# SX1276_e268v01a.net
KiCad netlist of a schematic drawn in Altium Designer
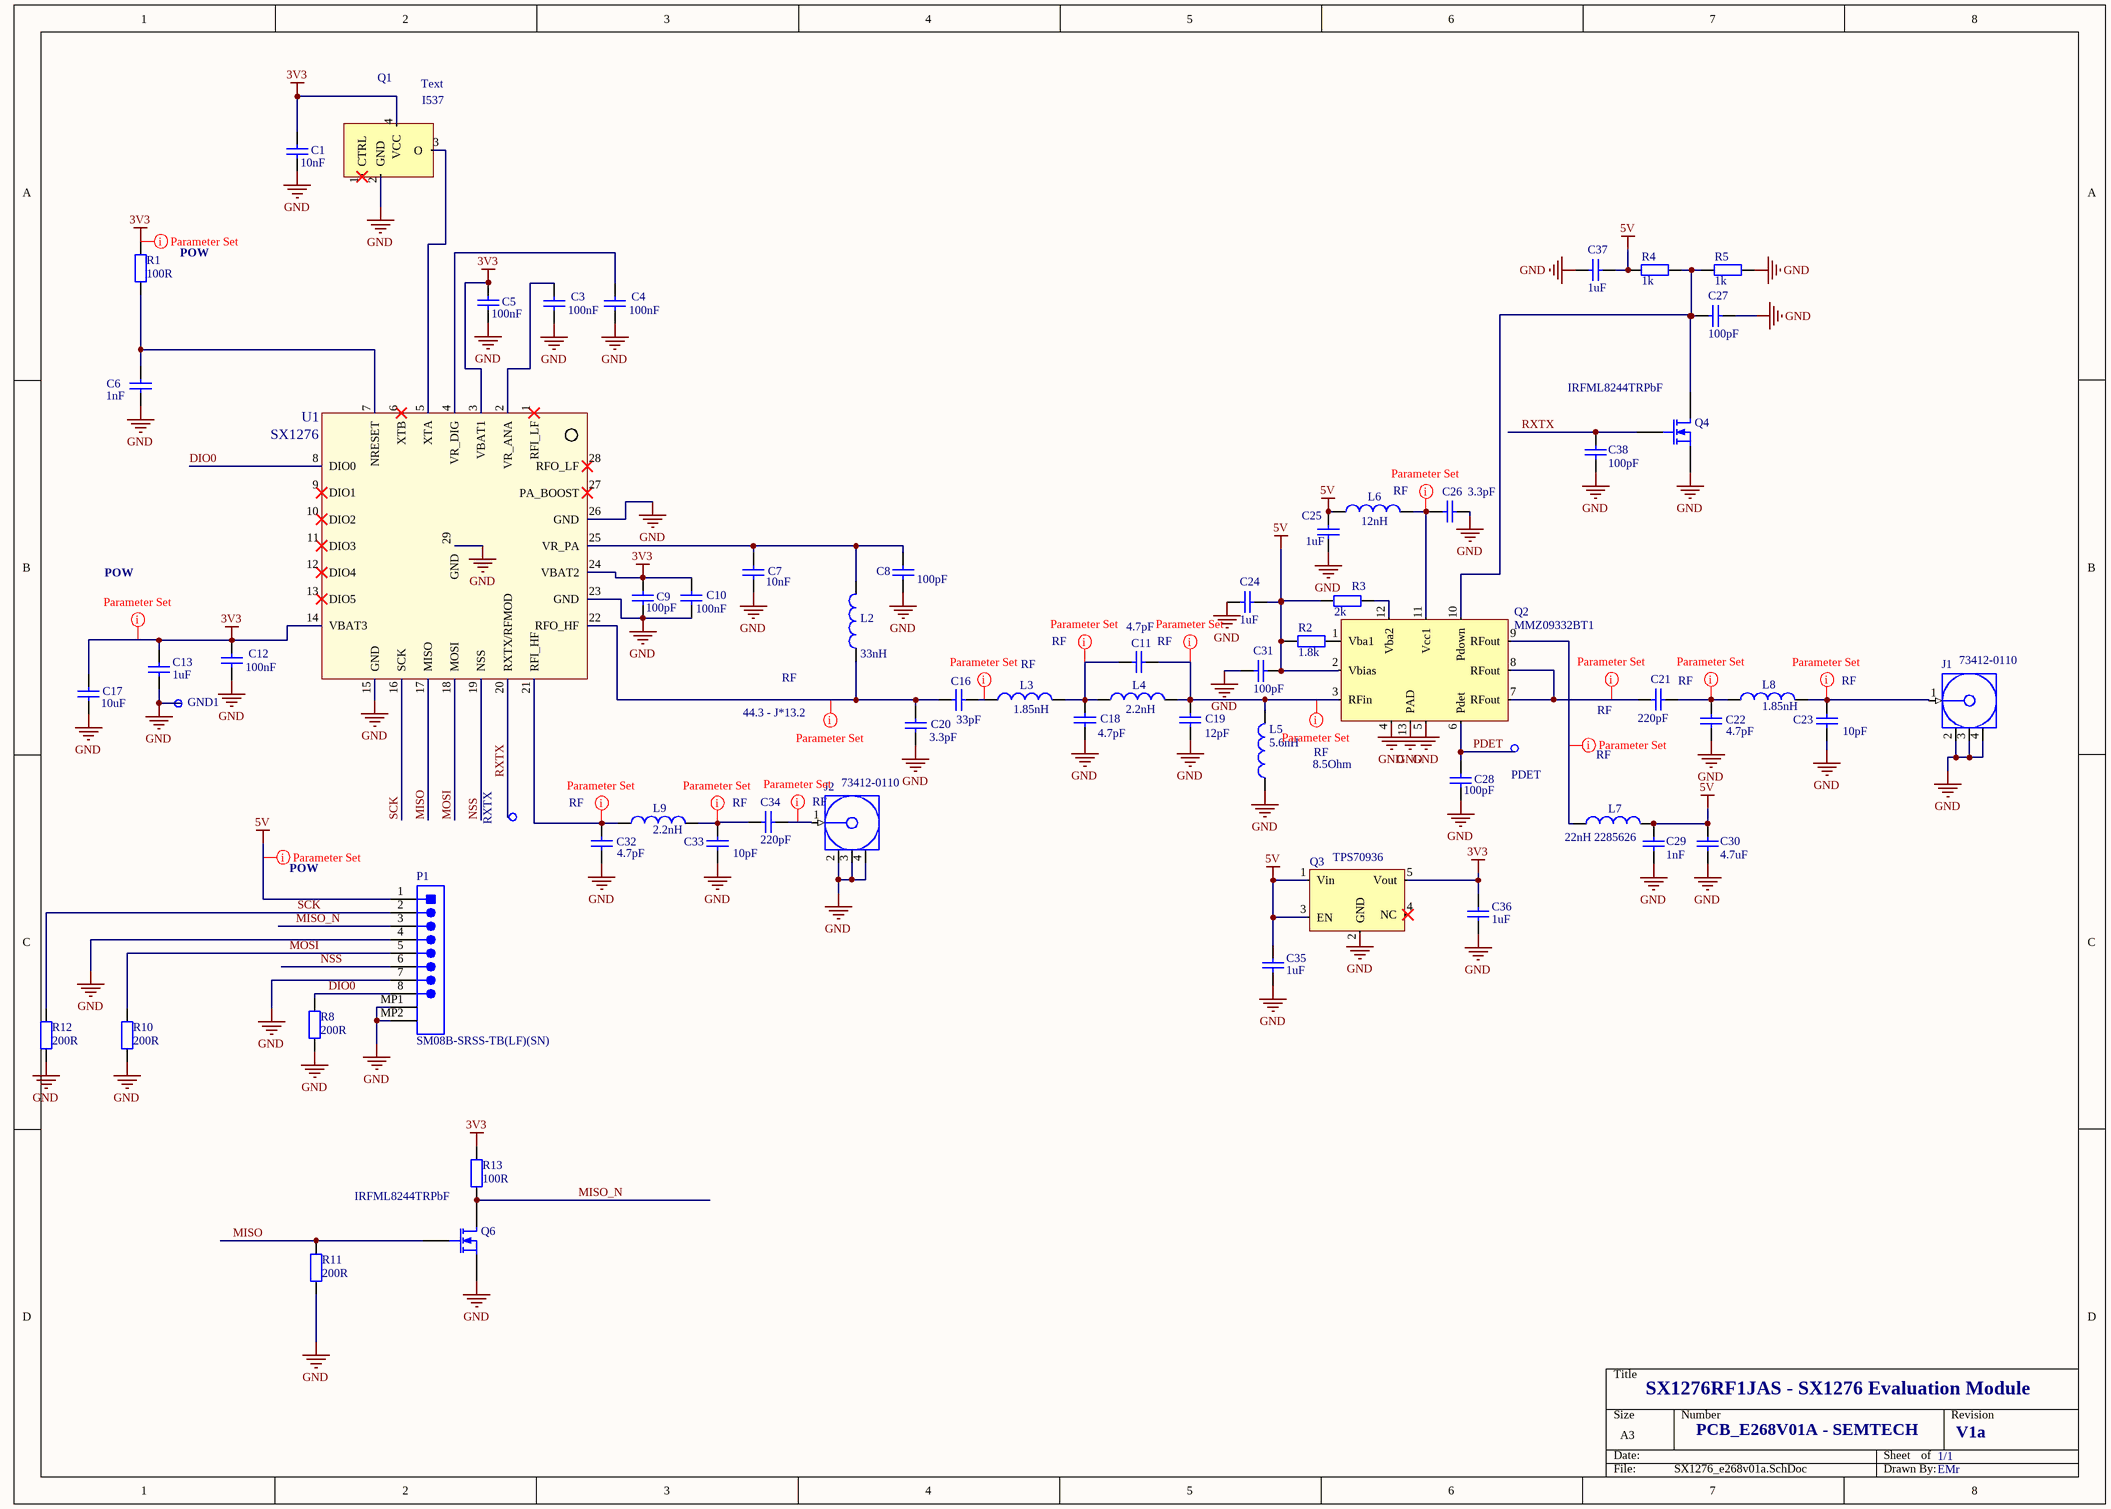
[diagram p0: SX1276_e268v01a.SchDoc]

(export (version "E")
  (design (tool "Eeschema 10.0.6"))
  (components
    (comp (ref "C1")
      (value "10nF")
      (footprint "rlc_402_smd")
      (description "Capacitor SMD")
      (fields (field (name "Comment") "Cap") (field (name "PUBLISHER") "Altium Limited"))
      (libsource (lib "SX1276_e268v01a") (part "Cap"))
    )
    (comp (ref "C3")
      (value "100nF")
      (footprint "rlc_402_smd")
      (description "Capacitor SMD")
      (fields (field (name "Comment") "Cap") (field (name "PUBLISHER") "Altium Limited"))
      (libsource (lib "SX1276_e268v01a") (part "Cap"))
    )
    (comp (ref "C4")
      (value "100nF")
      (footprint "rlc_402_smd")
      (description "Capacitor SMD")
      (fields (field (name "Comment") "Cap") (field (name "PUBLISHER") "Altium Limited"))
      (libsource (lib "SX1276_e268v01a") (part "Cap"))
    )
    (comp (ref "C5")
      (value "100nF")
      (footprint "rlc_402_smd")
      (description "Capacitor SMD")
      (fields (field (name "Comment") "Cap") (field (name "PUBLISHER") "Altium Limited"))
      (libsource (lib "SX1276_e268v01a") (part "Cap"))
    )
    (comp (ref "C6")
      (value "1nF")
      (footprint "rlc_402_smd")
      (description "Capacitor SMD")
      (fields (field (name "Comment") "Cap") (field (name "PUBLISHER") "Altium Limited"))
      (libsource (lib "SX1276_e268v01a") (part "Cap"))
    )
    (comp (ref "C7")
      (value "10nF")
      (footprint "rlc_402_smd")
      (description "Capacitor SMD")
      (fields (field (name "Comment") "Cap") (field (name "PUBLISHER") "Altium Limited"))
      (libsource (lib "SX1276_e268v01a") (part "Cap"))
    )
    (comp (ref "C8")
      (value "100pF")
      (footprint "rlc_402_smd")
      (description "Capacitor SMD")
      (fields (field (name "Comment") "Cap") (field (name "PUBLISHER") "Altium Limited"))
      (libsource (lib "SX1276_e268v01a") (part "Cap"))
    )
    (comp (ref "C9")
      (value "100pF")
      (footprint "rlc_402_smd")
      (description "Capacitor SMD")
      (fields (field (name "Comment") "Cap") (field (name "PUBLISHER") "Altium Limited"))
      (libsource (lib "SX1276_e268v01a") (part "Cap"))
    )
    (comp (ref "C10")
      (value "100nF")
      (footprint "rlc_402_smd")
      (description "Capacitor SMD")
      (fields (field (name "Comment") "Cap") (field (name "PUBLISHER") "Altium Limited"))
      (libsource (lib "SX1276_e268v01a") (part "Cap"))
    )
    (comp (ref "C11")
      (value "4.7pF")
      (footprint "rlc_402_smd")
      (description "Capacitor SMD")
      (fields (field (name "Comment") "Cap") (field (name "PUBLISHER") "Altium Limited"))
      (libsource (lib "SX1276_e268v01a") (part "Cap"))
    )
    (comp (ref "C12")
      (value "100nF")
      (footprint "rlc_402_smd")
      (description "Capacitor SMD")
      (fields (field (name "Comment") "Cap") (field (name "PUBLISHER") "Altium Limited"))
      (libsource (lib "SX1276_e268v01a") (part "Cap"))
    )
    (comp (ref "C13")
      (value "1uF")
      (footprint "rlc_603_smd")
      (description "Capacitor (Semiconductor SIM Model)")
      (fields (field (name "Comment") "Cap Semi") (field (name "PUBLISHER") "Altium Limited"))
      (libsource (lib "SX1276_e268v01a") (part "Cap Semi"))
    )
    (comp (ref "C16")
      (value "33pF")
      (footprint "rlc_402_smd")
      (description "Capacitor SMD")
      (fields (field (name "Comment") "Cap") (field (name "PUBLISHER") "Altium Limited"))
      (libsource (lib "SX1276_e268v01a") (part "Cap"))
    )
    (comp (ref "C17")
      (value "10uF")
      (footprint "rlc_805_smd")
      (description "Capacitor SMD")
      (fields (field (name "Comment") "Cap") (field (name "PUBLISHER") "Altium Limited"))
      (libsource (lib "SX1276_e268v01a") (part "Cap"))
    )
    (comp (ref "C18")
      (value "4.7pF")
      (footprint "rlc_402_smd")
      (description "Capacitor SMD")
      (fields (field (name "Comment") "Cap") (field (name "PUBLISHER") "Altium Limited"))
      (libsource (lib "SX1276_e268v01a") (part "Cap"))
    )
    (comp (ref "C19")
      (value "12pF")
      (footprint "rlc_402_smd")
      (description "Capacitor SMD")
      (fields (field (name "Comment") "Cap") (field (name "PUBLISHER") "Altium Limited"))
      (libsource (lib "SX1276_e268v01a") (part "Cap"))
    )
    (comp (ref "C20")
      (value "3.3pF")
      (footprint "rlc_402_smd")
      (description "Capacitor SMD")
      (fields (field (name "Comment") "Cap") (field (name "PUBLISHER") "Altium Limited"))
      (libsource (lib "SX1276_e268v01a") (part "Cap"))
    )
    (comp (ref "C21")
      (value "220pF")
      (footprint "rlc_402_smd")
      (description "Capacitor SMD")
      (fields (field (name "Comment") "Cap") (field (name "PUBLISHER") "Altium Limited"))
      (libsource (lib "SX1276_e268v01a") (part "Cap"))
    )
    (comp (ref "C22")
      (value "4.7pF")
      (footprint "rlc_402_smd")
      (description "Capacitor SMD")
      (fields (field (name "Comment") "Cap") (field (name "PUBLISHER") "Altium Limited"))
      (libsource (lib "SX1276_e268v01a") (part "Cap"))
    )
    (comp (ref "C23")
      (value "10pF")
      (footprint "rlc_402_smd")
      (description "Capacitor SMD")
      (fields (field (name "Comment") "Cap") (field (name "PUBLISHER") "Altium Limited"))
      (libsource (lib "SX1276_e268v01a") (part "Cap"))
    )
    (comp (ref "C24")
      (value "1uF")
      (footprint "rlc_603_smd")
      (description "Capacitor SMD")
      (fields (field (name "Comment") "Cap") (field (name "PUBLISHER") "Altium Limited"))
      (libsource (lib "SX1276_e268v01a") (part "Cap"))
    )
    (comp (ref "C25")
      (value "1uF")
      (footprint "rlc_603_smd")
      (description "Capacitor SMD")
      (fields (field (name "Comment") "Cap") (field (name "PUBLISHER") "Altium Limited"))
      (libsource (lib "SX1276_e268v01a") (part "Cap"))
    )
    (comp (ref "C26")
      (value "3.3pF")
      (footprint "rlc_402_smd")
      (description "Capacitor SMD")
      (fields (field (name "Comment") "Cap") (field (name "PUBLISHER") "Altium Limited"))
      (libsource (lib "SX1276_e268v01a") (part "Cap"))
    )
    (comp (ref "C27")
      (value "100pF")
      (footprint "rlc_402_smd")
      (description "Capacitor SMD")
      (fields (field (name "Comment") "Cap") (field (name "PUBLISHER") "Altium Limited"))
      (libsource (lib "SX1276_e268v01a") (part "Cap"))
    )
    (comp (ref "C28")
      (value "100pF")
      (footprint "rlc_402_smd")
      (description "Capacitor SMD")
      (fields (field (name "Comment") "Cap") (field (name "PUBLISHER") "Altium Limited"))
      (libsource (lib "SX1276_e268v01a") (part "Cap"))
    )
    (comp (ref "C29")
      (value "1nF")
      (footprint "rlc_402_smd")
      (description "Capacitor SMD")
      (fields (field (name "Comment") "Cap") (field (name "PUBLISHER") "Altium Limited"))
      (libsource (lib "SX1276_e268v01a") (part "Cap"))
    )
    (comp (ref "C30")
      (value "4.7uF")
      (footprint "rlc_603_smd")
      (description "Capacitor SMD")
      (fields (field (name "Comment") "Cap") (field (name "PUBLISHER") "Altium Limited"))
      (libsource (lib "SX1276_e268v01a") (part "Cap"))
    )
    (comp (ref "C31")
      (value "100pF")
      (footprint "rlc_402_smd")
      (description "Capacitor SMD")
      (fields (field (name "Comment") "Cap") (field (name "PUBLISHER") "Altium Limited"))
      (libsource (lib "SX1276_e268v01a") (part "Cap"))
    )
    (comp (ref "C32")
      (value "4.7pF")
      (footprint "rlc_402_smd")
      (description "Capacitor SMD")
      (fields (field (name "Comment") "Cap") (field (name "PUBLISHER") "Altium Limited"))
      (libsource (lib "SX1276_e268v01a") (part "Cap"))
    )
    (comp (ref "C33")
      (value "10pF")
      (footprint "rlc_402_smd")
      (description "Capacitor SMD")
      (fields (field (name "Comment") "Cap") (field (name "PUBLISHER") "Altium Limited"))
      (libsource (lib "SX1276_e268v01a") (part "Cap"))
    )
    (comp (ref "C34")
      (value "220pF")
      (footprint "rlc_402_smd")
      (description "Capacitor SMD")
      (fields (field (name "Comment") "Cap") (field (name "PUBLISHER") "Altium Limited"))
      (libsource (lib "SX1276_e268v01a") (part "Cap"))
    )
    (comp (ref "C35")
      (value "1uF")
      (footprint "rlc_603_smd")
      (description "Capacitor (Semiconductor SIM Model)")
      (fields (field (name "Comment") "Cap Semi") (field (name "PUBLISHER") "Altium Limited"))
      (libsource (lib "SX1276_e268v01a") (part "Cap Semi"))
    )
    (comp (ref "C36")
      (value "1uF")
      (footprint "rlc_603_smd")
      (description "Capacitor (Semiconductor SIM Model)")
      (fields (field (name "Comment") "Cap Semi") (field (name "PUBLISHER") "Altium Limited"))
      (libsource (lib "SX1276_e268v01a") (part "Cap Semi"))
    )
    (comp (ref "C37")
      (value "1uF")
      (footprint "rlc_603_smd")
      (description "Capacitor SMD")
      (fields (field (name "Comment") "Cap") (field (name "PUBLISHER") "Altium Limited"))
      (libsource (lib "SX1276_e268v01a") (part "Cap"))
    )
    (comp (ref "C38")
      (value "100pF")
      (footprint "rlc_402_smd")
      (description "Capacitor SMD")
      (fields (field (name "Comment") "Cap") (field (name "PUBLISHER") "Altium Limited"))
      (libsource (lib "SX1276_e268v01a") (part "Cap"))
    )
    (comp (ref "GND1")
      (value "Test Pin")
      (footprint "pin_1mm")
      (libsource (lib "SX1276_e268v01a") (part "test_pin"))
    )
    (comp (ref "J1")
      (value "73412-0110")
      (footprint "MOLX-73412-0110_V")
      (description "MCRF, PCB Vertical Jack Receptacle, 50 Ohm, 4-Pin SMD, RoHS, Tape and Reel")
      (libsource (lib "Altium Content Vault") (part "MOLX-73412-0110"))
    )
    (comp (ref "J2")
      (value "73412-0110")
      (footprint "MOLX-73412-0110_V")
      (description "MCRF, PCB Vertical Jack Receptacle, 50 Ohm, 4-Pin SMD, RoHS, Tape and Reel")
      (libsource (lib "Altium Content Vault") (part "MOLX-73412-0110"))
    )
    (comp (ref "L2")
      (value "33nH")
      (footprint "rlc_402_smd")
      (description "Inductor SMD")
      (fields (field (name "Comment") "Inductor") (field (name "PUBLISHER") "Altium Limited"))
      (libsource (lib "SX1276_e268v01a") (part "Inductor"))
    )
    (comp (ref "L3")
      (value "1.85nH")
      (footprint "rlc_402_smd")
      (description "Inductor SMD")
      (fields (field (name "Comment") "Inductor") (field (name "PUBLISHER") "Altium Limited"))
      (libsource (lib "SX1276_e268v01a") (part "Inductor"))
    )
    (comp (ref "L4")
      (value "2.2nH")
      (footprint "rlc_402_smd")
      (description "Inductor SMD")
      (fields (field (name "Comment") "Inductor") (field (name "PUBLISHER") "Altium Limited"))
      (libsource (lib "SX1276_e268v01a") (part "Inductor"))
    )
    (comp (ref "L5")
      (value "5.6nH")
      (footprint "rlc_402_smd")
      (description "Inductor SMD")
      (fields (field (name "Comment") "Inductor") (field (name "PUBLISHER") "Altium Limited"))
      (libsource (lib "SX1276_e268v01a") (part "Inductor"))
    )
    (comp (ref "L6")
      (value "12nH")
      (footprint "rlc_402_smd")
      (description "Inductor SMD")
      (fields (field (name "Comment") "Inductor") (field (name "PUBLISHER") "Altium Limited"))
      (libsource (lib "SX1276_e268v01a") (part "Inductor"))
    )
    (comp (ref "L7")
      (value "22nH 2285626")
      (footprint "rlc_402_smd")
      (description "Inductor SMD")
      (fields (field (name "Comment") "Inductor") (field (name "PUBLISHER") "Altium Limited"))
      (libsource (lib "SX1276_e268v01a") (part "Inductor"))
    )
    (comp (ref "L8")
      (value "1.85nH")
      (footprint "rlc_402_smd")
      (description "Inductor SMD")
      (fields (field (name "Comment") "Inductor") (field (name "PUBLISHER") "Altium Limited"))
      (libsource (lib "SX1276_e268v01a") (part "Inductor"))
    )
    (comp (ref "L9")
      (value "2.2nH")
      (footprint "rlc_402_smd")
      (description "Inductor SMD")
      (fields (field (name "Comment") "Inductor") (field (name "PUBLISHER") "Altium Limited"))
      (libsource (lib "SX1276_e268v01a") (part "Inductor"))
    )
    (comp (ref "P1")
      (value "SM08B-SRSS-TB(LF)(SN)")
      (footprint "JST-SM08B-SRSS-TB_V")
      (description "Male Header, Pitch 1 mm, 1 x 8 Position, Height 2.95 mm, -25 to 85 degC, RoHS, Tape and Reel")
      (fields (field (name "MANUFACTURER") "JST"))
      (libsource (lib "Altium Content Vault") (part "CN-1P-2M-R8"))
    )
    (comp (ref "PDET")
      (value "Test Pin")
      (footprint "pin_SMD")
      (libsource (lib "SX1276_e268v01a") (part "test_pin"))
    )
    (comp (ref "Q1")
      (value "I537")
      (footprint "nd3225da")
      (description "Termally Compensated External Oscillator")
      (libsource (lib "SX1276_e268v01a") (part "TCXO"))
    )
    (comp (ref "Q2")
      (value "MMZ09332BT1")
      (footprint "QFN3_3")
      (libsource (lib "Sender") (part "MMZ09332BT1"))
    )
    (comp (ref "Q3") (value "TPS70936") (footprint "SOT-23-5") (libsource (lib "Sender") (part "RT9086")))
    (comp (ref "Q4")
      (value "IRFML8244TRPbF")
      (footprint "SOT23_MOSFET")
      (description "N-Channel MOSFET")
      (fields (field (name "PUBLISHER") "Altium Limited"))
      (libsource (lib "Miscellaneous Devices") (part "MOSFET-N"))
    )
    (comp (ref "Q6")
      (value "IRFML8244TRPbF")
      (footprint "SOT23_MOSFET")
      (description "N-Channel MOSFET")
      (fields (field (name "PUBLISHER") "Altium Limited"))
      (libsource (lib "Miscellaneous Devices") (part "MOSFET-N"))
    )
    (comp (ref "R1")
      (value "100R")
      (footprint "rlc_402_smd")
      (description "Resistor SMD - IEC symbol version")
      (fields (field (name "Comment") "Resistor"))
      (libsource (lib "") (part "Resistor_2"))
    )
    (comp (ref "R2")
      (value "1.8k")
      (footprint "rlc_402_smd")
      (description "Resistor SMD - IEC symbol version")
      (fields (field (name "Comment") "Resistor"))
      (libsource (lib "SX1276_e268v01a") (part "Resistor"))
    )
    (comp (ref "R3")
      (value "2k")
      (footprint "rlc_402_smd")
      (description "Resistor SMD - IEC symbol version")
      (fields (field (name "Comment") "Resistor"))
      (libsource (lib "SX1276_e268v01a") (part "Resistor"))
    )
    (comp (ref "R4")
      (value "1k")
      (footprint "rlc_402_smd")
      (description "Resistor SMD - IEC symbol version")
      (fields (field (name "Comment") "Resistor"))
      (libsource (lib "SX1276_e268v01a") (part "Resistor"))
    )
    (comp (ref "R5")
      (value "1k")
      (footprint "rlc_402_smd")
      (description "Resistor SMD - IEC symbol version")
      (fields (field (name "Comment") "Resistor"))
      (libsource (lib "SX1276_e268v01a") (part "Resistor"))
    )
    (comp (ref "R8")
      (value "200R")
      (footprint "rlc_402_smd")
      (description "Resistor SMD - IEC symbol version")
      (fields (field (name "Comment") "Resistor"))
      (libsource (lib "") (part "Resistor_1"))
    )
    (comp (ref "R10")
      (value "200R")
      (footprint "rlc_402_smd")
      (description "Resistor SMD - IEC symbol version")
      (fields (field (name "Comment") "Resistor"))
      (libsource (lib "") (part "Resistor_1"))
    )
    (comp (ref "R11")
      (value "200R")
      (footprint "rlc_402_smd")
      (description "Resistor SMD - IEC symbol version")
      (fields (field (name "Comment") "Resistor"))
      (libsource (lib "") (part "Resistor_1"))
    )
    (comp (ref "R12")
      (value "200R")
      (footprint "rlc_402_smd")
      (description "Resistor SMD - IEC symbol version")
      (fields (field (name "Comment") "Resistor"))
      (libsource (lib "") (part "Resistor_1"))
    )
    (comp (ref "R13")
      (value "100R")
      (footprint "rlc_402_smd")
      (description "Resistor SMD - IEC symbol version")
      (fields (field (name "Comment") "Resistor"))
      (libsource (lib "") (part "Resistor_1"))
    )
    (comp (ref "RXTX")
      (value "Test Pin")
      (footprint "pin_SMD")
      (libsource (lib "SX1276_e268v01a") (part "test_pin"))
    )
    (comp (ref "U1")
      (value "SX1276")
      (footprint "vqfn28_6x6mm")
      (description "SX1276 - Low Power Integrated UHF Transceiver with loRa Modem")
      (libsource (lib "SX1276_e268v01a") (part "SX1276"))
    )
  )
  (nets
    (net (code "1") (name "/DIO0") (class "Default")
      (node (ref "P1") (pin "8") (pinfunction "8_8") (pintype "passive"))
      (node (ref "R8") (pin "1") (pinfunction "1_1") (pintype "passive"))
      (node (ref "U1") (pin "8") (pinfunction "DIO0_8") (pintype "passive"))
    )
    (net (code "2") (name "/MISO") (class "Default")
      (node (ref "Q6") (pin "G") (pinfunction "G_G") (pintype "passive"))
      (node (ref "R11") (pin "1") (pinfunction "1_1") (pintype "passive"))
      (node (ref "U1") (pin "17") (pinfunction "MISO_17") (pintype "passive"))
    )
    (net (code "3") (name "/MISO_N") (class "Default")
      (node (ref "P1") (pin "3") (pinfunction "3_3") (pintype "passive"))
      (node (ref "Q6") (pin "D") (pinfunction "D_D") (pintype "passive"))
      (node (ref "R13") (pin "2") (pinfunction "2_2") (pintype "passive"))
    )
    (net (code "4") (name "/MOSI") (class "Default")
      (node (ref "P1") (pin "5") (pinfunction "5_5") (pintype "passive"))
      (node (ref "R10") (pin "1") (pinfunction "1_1") (pintype "passive"))
      (node (ref "U1") (pin "18") (pinfunction "MOSI_18") (pintype "passive"))
    )
    (net (code "5") (name "/NSS") (class "Default")
      (node (ref "P1") (pin "6") (pinfunction "6_6") (pintype "passive"))
      (node (ref "U1") (pin "19") (pinfunction "NSS_19") (pintype "passive"))
    )
    (net (code "6") (name "/PDET") (class "Default")
      (node (ref "C28") (pin "2") (pinfunction "2_2") (pintype "passive"))
      (node (ref "PDET") (pin "1") (pinfunction "pin_1") (pintype "passive"))
      (node (ref "Q2") (pin "6") (pinfunction "Pdet_6") (pintype "passive"))
    )
    (net (code "7") (name "/RXTX") (class "Default")
      (node (ref "C38") (pin "1") (pinfunction "1_1") (pintype "passive"))
      (node (ref "Q4") (pin "G") (pinfunction "G_G") (pintype "passive"))
      (node (ref "RXTX") (pin "1") (pinfunction "pin_1") (pintype "passive"))
      (node (ref "U1") (pin "20") (pinfunction "RXTX/RFMOD_20") (pintype "passive"))
    )
    (net (code "8") (name "/SCK") (class "Default")
      (node (ref "P1") (pin "2") (pinfunction "2_2") (pintype "passive"))
      (node (ref "R12") (pin "1") (pinfunction "1_1") (pintype "passive"))
      (node (ref "U1") (pin "16") (pinfunction "SCK_16") (pintype "passive"))
    )
    (net (code "9") (name "3V3") (class "Default")
      (node (ref "C1") (pin "2") (pinfunction "2_2") (pintype "passive"))
      (node (ref "C10") (pin "2") (pinfunction "2_2") (pintype "passive"))
      (node (ref "C12") (pin "2") (pinfunction "2_2") (pintype "passive"))
      (node (ref "C13") (pin "2") (pinfunction "2_2") (pintype "passive"))
      (node (ref "C17") (pin "2") (pinfunction "2_2") (pintype "passive"))
      (node (ref "C36") (pin "2") (pinfunction "2_2") (pintype "passive"))
      (node (ref "C5") (pin "2") (pinfunction "2_2") (pintype "passive"))
      (node (ref "C9") (pin "2") (pinfunction "2_2") (pintype "passive"))
      (node (ref "Q1") (pin "4") (pinfunction "VCC_4") (pintype "passive"))
      (node (ref "Q3") (pin "5") (pinfunction "Vout_5") (pintype "passive"))
      (node (ref "R1") (pin "2") (pinfunction "2_2") (pintype "passive"))
      (node (ref "R13") (pin "1") (pinfunction "1_1") (pintype "passive"))
      (node (ref "U1") (pin "14") (pinfunction "VBAT3_14") (pintype "passive"))
      (node (ref "U1") (pin "24") (pinfunction "VBAT2_24") (pintype "passive"))
      (node (ref "U1") (pin "3") (pinfunction "VBAT1_3") (pintype "passive"))
    )
    (net (code "10") (name "5V") (class "Default")
      (node (ref "C24") (pin "1") (pinfunction "1_1") (pintype "passive"))
      (node (ref "C25") (pin "2") (pinfunction "2_2") (pintype "passive"))
      (node (ref "C29") (pin "2") (pinfunction "2_2") (pintype "passive"))
      (node (ref "C30") (pin "2") (pinfunction "2_2") (pintype "passive"))
      (node (ref "C31") (pin "2") (pinfunction "2_2") (pintype "passive"))
      (node (ref "C35") (pin "2") (pinfunction "2_2") (pintype "passive"))
      (node (ref "C37") (pin "1") (pinfunction "1_1") (pintype "passive"))
      (node (ref "L6") (pin "1") (pinfunction "1_1") (pintype "passive"))
      (node (ref "L7") (pin "2") (pinfunction "2_2") (pintype "passive"))
      (node (ref "P1") (pin "1") (pinfunction "1_1") (pintype "passive"))
      (node (ref "Q2") (pin "2") (pinfunction "Vbias_2") (pintype "passive"))
      (node (ref "Q3") (pin "1") (pinfunction "Vin_1") (pintype "passive"))
      (node (ref "Q3") (pin "3") (pinfunction "EN_3") (pintype "passive"))
      (node (ref "R2") (pin "2") (pinfunction "2_2") (pintype "passive"))
      (node (ref "R3") (pin "2") (pinfunction "2_2") (pintype "passive"))
      (node (ref "R4") (pin "2") (pinfunction "2_2") (pintype "passive"))
    )
    (net (code "11") (name "GND") (class "Default")
      (node (ref "C1") (pin "1") (pinfunction "1_1") (pintype "passive"))
      (node (ref "C10") (pin "1") (pinfunction "1_1") (pintype "passive"))
      (node (ref "C12") (pin "1") (pinfunction "1_1") (pintype "passive"))
      (node (ref "C13") (pin "1") (pinfunction "1_1") (pintype "passive"))
      (node (ref "C17") (pin "1") (pinfunction "1_1") (pintype "passive"))
      (node (ref "C18") (pin "1") (pinfunction "1_1") (pintype "passive"))
      (node (ref "C19") (pin "1") (pinfunction "1_1") (pintype "passive"))
      (node (ref "C20") (pin "1") (pinfunction "1_1") (pintype "passive"))
      (node (ref "C22") (pin "1") (pinfunction "1_1") (pintype "passive"))
      (node (ref "C23") (pin "1") (pinfunction "1_1") (pintype "passive"))
      (node (ref "C24") (pin "2") (pinfunction "2_2") (pintype "passive"))
      (node (ref "C25") (pin "1") (pinfunction "1_1") (pintype "passive"))
      (node (ref "C26") (pin "2") (pinfunction "2_2") (pintype "passive"))
      (node (ref "C27") (pin "1") (pinfunction "1_1") (pintype "passive"))
      (node (ref "C28") (pin "1") (pinfunction "1_1") (pintype "passive"))
      (node (ref "C29") (pin "1") (pinfunction "1_1") (pintype "passive"))
      (node (ref "C3") (pin "1") (pinfunction "1_1") (pintype "passive"))
      (node (ref "C30") (pin "1") (pinfunction "1_1") (pintype "passive"))
      (node (ref "C31") (pin "1") (pinfunction "1_1") (pintype "passive"))
      (node (ref "C32") (pin "1") (pinfunction "1_1") (pintype "passive"))
      (node (ref "C33") (pin "1") (pinfunction "1_1") (pintype "passive"))
      (node (ref "C35") (pin "1") (pinfunction "1_1") (pintype "passive"))
      (node (ref "C36") (pin "1") (pinfunction "1_1") (pintype "passive"))
      (node (ref "C37") (pin "2") (pinfunction "2_2") (pintype "passive"))
      (node (ref "C38") (pin "2") (pinfunction "2_2") (pintype "passive"))
      (node (ref "C4") (pin "1") (pinfunction "1_1") (pintype "passive"))
      (node (ref "C5") (pin "1") (pinfunction "1_1") (pintype "passive"))
      (node (ref "C6") (pin "2") (pinfunction "2_2") (pintype "passive"))
      (node (ref "C7") (pin "1") (pinfunction "1_1") (pintype "passive"))
      (node (ref "C8") (pin "1") (pinfunction "1_1") (pintype "passive"))
      (node (ref "C9") (pin "1") (pinfunction "1_1") (pintype "passive"))
      (node (ref "GND1") (pin "1") (pinfunction "pin_1") (pintype "passive"))
      (node (ref "J1") (pin "2") (pinfunction "GND_2") (pintype "power_in"))
      (node (ref "J1") (pin "3") (pinfunction "GND_3") (pintype "power_in"))
      (node (ref "J1") (pin "4") (pinfunction "GND_4") (pintype "power_in"))
      (node (ref "J2") (pin "2") (pinfunction "GND_2") (pintype "power_in"))
      (node (ref "J2") (pin "3") (pinfunction "GND_3") (pintype "power_in"))
      (node (ref "J2") (pin "4") (pinfunction "GND_4") (pintype "power_in"))
      (node (ref "L5") (pin "1") (pinfunction "1_1") (pintype "passive"))
      (node (ref "P1") (pin "4") (pinfunction "4_4") (pintype "passive"))
      (node (ref "P1") (pin "7") (pinfunction "7_7") (pintype "passive"))
      (node (ref "P1") (pin "MP1") (pinfunction "MP1_MP1") (pintype "passive"))
      (node (ref "P1") (pin "MP2") (pinfunction "MP2_MP2") (pintype "passive"))
      (node (ref "Q1") (pin "2") (pinfunction "GND_2") (pintype "passive"))
      (node (ref "Q2") (pin "13") (pinfunction "PAD_13") (pintype "passive"))
      (node (ref "Q2") (pin "4") (pintype "passive"))
      (node (ref "Q2") (pin "5") (pintype "passive"))
      (node (ref "Q3") (pin "2") (pinfunction "GND_2") (pintype "passive"))
      (node (ref "Q4") (pin "S") (pinfunction "S_S") (pintype "passive"))
      (node (ref "Q6") (pin "S") (pinfunction "S_S") (pintype "passive"))
      (node (ref "R10") (pin "2") (pinfunction "2_2") (pintype "passive"))
      (node (ref "R11") (pin "2") (pinfunction "2_2") (pintype "passive"))
      (node (ref "R12") (pin "2") (pinfunction "2_2") (pintype "passive"))
      (node (ref "R5") (pin "1") (pinfunction "1_1") (pintype "passive"))
      (node (ref "R8") (pin "2") (pinfunction "2_2") (pintype "passive"))
      (node (ref "U1") (pin "15") (pinfunction "GND_15") (pintype "passive"))
      (node (ref "U1") (pin "23") (pinfunction "GND_23") (pintype "passive"))
      (node (ref "U1") (pin "26") (pinfunction "GND_26") (pintype "passive"))
      (node (ref "U1") (pin "29") (pinfunction "GND_29") (pintype "passive"))
    )
    (net (code "12") (name "Net-(C11-Pad2)") (class "Default")
      (node (ref "C11") (pin "2") (pinfunction "2_2") (pintype "passive"))
      (node (ref "C18") (pin "2") (pinfunction "2_2") (pintype "passive"))
      (node (ref "L3") (pin "2") (pinfunction "2_2") (pintype "passive"))
      (node (ref "L4") (pin "1") (pinfunction "1_1") (pintype "passive"))
    )
    (net (code "13") (name "Net-(C16-Pad1)") (class "Default")
      (node (ref "C16") (pin "1") (pinfunction "1_1") (pintype "passive"))
      (node (ref "L3") (pin "1") (pinfunction "1_1") (pintype "passive"))
    )
    (net (code "14") (name "Net-(C21-Pad1)") (class "Default")
      (node (ref "C21") (pin "1") (pinfunction "1_1") (pintype "passive"))
      (node (ref "C22") (pin "2") (pinfunction "2_2") (pintype "passive"))
      (node (ref "L8") (pin "1") (pinfunction "1_1") (pintype "passive"))
    )
    (net (code "15") (name "Net-(C21-Pad2)") (class "Default")
      (node (ref "C21") (pin "2") (pinfunction "2_2") (pintype "passive"))
      (node (ref "Q2") (pin "7") (pinfunction "RFout_7") (pintype "passive"))
      (node (ref "Q2") (pin "8") (pinfunction "RFout_8") (pintype "passive"))
    )
    (net (code "16") (name "Net-(C33-Pad2)") (class "Default")
      (node (ref "C33") (pin "2") (pinfunction "2_2") (pintype "passive"))
      (node (ref "C34") (pin "2") (pinfunction "2_2") (pintype "passive"))
      (node (ref "L9") (pin "2") (pinfunction "2_2") (pintype "passive"))
    )
    (net (code "17") (name "Net-(J1-SIGNAL)") (class "Default")
      (node (ref "C23") (pin "2") (pinfunction "2_2") (pintype "passive"))
      (node (ref "J1") (pin "1") (pinfunction "SIGNAL_1") (pintype "input"))
      (node (ref "L8") (pin "2") (pinfunction "2_2") (pintype "passive"))
    )
    (net (code "18") (name "Net-(J2-SIGNAL)") (class "Default")
      (node (ref "C34") (pin "1") (pinfunction "1_1") (pintype "passive"))
      (node (ref "J2") (pin "1") (pinfunction "SIGNAL_1") (pintype "input"))
    )
    (net (code "19") (name "Net-(L7-Pad1)") (class "Default")
      (node (ref "L7") (pin "1") (pinfunction "1_1") (pintype "passive"))
      (node (ref "Q2") (pin "9") (pinfunction "RFout_9") (pintype "passive"))
    )
    (net (code "20") (name "Net-(Q1-O)") (class "Default")
      (node (ref "Q1") (pin "3") (pinfunction "O_3") (pintype "passive"))
      (node (ref "U1") (pin "5") (pinfunction "XTA_5") (pintype "passive"))
    )
    (net (code "21") (name "Net-(Q2-Pdown)") (class "Default")
      (node (ref "C27") (pin "2") (pinfunction "2_2") (pintype "passive"))
      (node (ref "Q2") (pin "10") (pinfunction "Pdown_10") (pintype "passive"))
      (node (ref "Q4") (pin "D") (pinfunction "D_D") (pintype "passive"))
      (node (ref "R4") (pin "1") (pinfunction "1_1") (pintype "passive"))
      (node (ref "R5") (pin "2") (pinfunction "2_2") (pintype "passive"))
    )
    (net (code "22") (name "Net-(Q2-RFin)") (class "Default")
      (node (ref "C11") (pin "1") (pinfunction "1_1") (pintype "passive"))
      (node (ref "C19") (pin "2") (pinfunction "2_2") (pintype "passive"))
      (node (ref "L4") (pin "2") (pinfunction "2_2") (pintype "passive"))
      (node (ref "L5") (pin "2") (pinfunction "2_2") (pintype "passive"))
      (node (ref "Q2") (pin "3") (pinfunction "RFin_3") (pintype "passive"))
    )
    (net (code "23") (name "Net-(Q2-Vba1)") (class "Default")
      (node (ref "Q2") (pin "1") (pinfunction "Vba1_1") (pintype "passive"))
      (node (ref "R2") (pin "1") (pinfunction "1_1") (pintype "passive"))
    )
    (net (code "24") (name "Net-(Q2-Vba2)") (class "Default")
      (node (ref "Q2") (pin "12") (pinfunction "Vba2_12") (pintype "passive"))
      (node (ref "R3") (pin "1") (pinfunction "1_1") (pintype "passive"))
    )
    (net (code "25") (name "Net-(Q2-Vcc1)") (class "Default")
      (node (ref "C26") (pin "1") (pinfunction "1_1") (pintype "passive"))
      (node (ref "L6") (pin "2") (pinfunction "2_2") (pintype "passive"))
      (node (ref "Q2") (pin "11") (pinfunction "Vcc1_11") (pintype "passive"))
    )
    (net (code "26") (name "Net-(U1-NRESET)") (class "Default")
      (node (ref "C6") (pin "1") (pinfunction "1_1") (pintype "passive"))
      (node (ref "R1") (pin "1") (pinfunction "1_1") (pintype "passive"))
      (node (ref "U1") (pin "7") (pinfunction "NRESET_7") (pintype "passive"))
    )
    (net (code "27") (name "Net-(U1-RFI_HF)") (class "Default")
      (node (ref "C32") (pin "2") (pinfunction "2_2") (pintype "passive"))
      (node (ref "L9") (pin "1") (pinfunction "1_1") (pintype "passive"))
      (node (ref "U1") (pin "21") (pinfunction "RFI_HF_21") (pintype "passive"))
    )
    (net (code "28") (name "Net-(U1-RFO_HF)") (class "Default")
      (node (ref "C16") (pin "2") (pinfunction "2_2") (pintype "passive"))
      (node (ref "C20") (pin "2") (pinfunction "2_2") (pintype "passive"))
      (node (ref "L2") (pin "1") (pinfunction "1_1") (pintype "passive"))
      (node (ref "U1") (pin "22") (pinfunction "RFO_HF_22") (pintype "passive"))
    )
    (net (code "29") (name "Net-(U1-VR_ANA)") (class "Default")
      (node (ref "C3") (pin "2") (pinfunction "2_2") (pintype "passive"))
      (node (ref "U1") (pin "2") (pinfunction "VR_ANA_2") (pintype "passive"))
    )
    (net (code "30") (name "Net-(U1-VR_DIG)") (class "Default")
      (node (ref "C4") (pin "2") (pinfunction "2_2") (pintype "passive"))
      (node (ref "U1") (pin "4") (pinfunction "VR_DIG_4") (pintype "passive"))
    )
    (net (code "31") (name "Net-(U1-VR_PA)") (class "Default")
      (node (ref "C7") (pin "2") (pinfunction "2_2") (pintype "passive"))
      (node (ref "C8") (pin "2") (pinfunction "2_2") (pintype "passive"))
      (node (ref "L2") (pin "2") (pinfunction "2_2") (pintype "passive"))
      (node (ref "U1") (pin "25") (pinfunction "VR_PA_25") (pintype "passive"))
    )
    (net (code "32") (name "unconnected-(Q1-CTRL-Pad1)") (class "Default")
      (node (ref "Q1") (pin "1") (pinfunction "CTRL_1") (pintype "passive+no_connect"))
    )
    (net (code "33") (name "unconnected-(Q3-NC-Pad4)") (class "Default")
      (node (ref "Q3") (pin "4") (pinfunction "NC_4") (pintype "passive+no_connect"))
    )
    (net (code "34") (name "unconnected-(U1-DIO1-Pad9)") (class "Default")
      (node (ref "U1") (pin "9") (pinfunction "DIO1_9") (pintype "passive+no_connect"))
    )
    (net (code "35") (name "unconnected-(U1-DIO2-Pad10)") (class "Default")
      (node (ref "U1") (pin "10") (pinfunction "DIO2_10") (pintype "passive+no_connect"))
    )
    (net (code "36") (name "unconnected-(U1-DIO3-Pad11)") (class "Default")
      (node (ref "U1") (pin "11") (pinfunction "DIO3_11") (pintype "passive+no_connect"))
    )
    (net (code "37") (name "unconnected-(U1-DIO4-Pad12)") (class "Default")
      (node (ref "U1") (pin "12") (pinfunction "DIO4_12") (pintype "passive+no_connect"))
    )
    (net (code "38") (name "unconnected-(U1-DIO5-Pad13)") (class "Default")
      (node (ref "U1") (pin "13") (pinfunction "DIO5_13") (pintype "passive+no_connect"))
    )
    (net (code "39") (name "unconnected-(U1-PA_BOOST-Pad27)") (class "Default")
      (node (ref "U1") (pin "27") (pinfunction "PA_BOOST_27") (pintype "passive+no_connect"))
    )
    (net (code "40") (name "unconnected-(U1-RFI_LF-Pad1)") (class "Default")
      (node (ref "U1") (pin "1") (pinfunction "RFI_LF_1") (pintype "passive+no_connect"))
    )
    (net (code "41") (name "unconnected-(U1-RFO_LF-Pad28)") (class "Default")
      (node (ref "U1") (pin "28") (pinfunction "RFO_LF_28") (pintype "passive+no_connect"))
    )
    (net (code "42") (name "unconnected-(U1-XTB-Pad6)") (class "Default")
      (node (ref "U1") (pin "6") (pinfunction "XTB_6") (pintype "passive+no_connect"))
    )
  )
)
